# MAX6675.net
KiCad netlist of a schematic drawn in Altium Designer
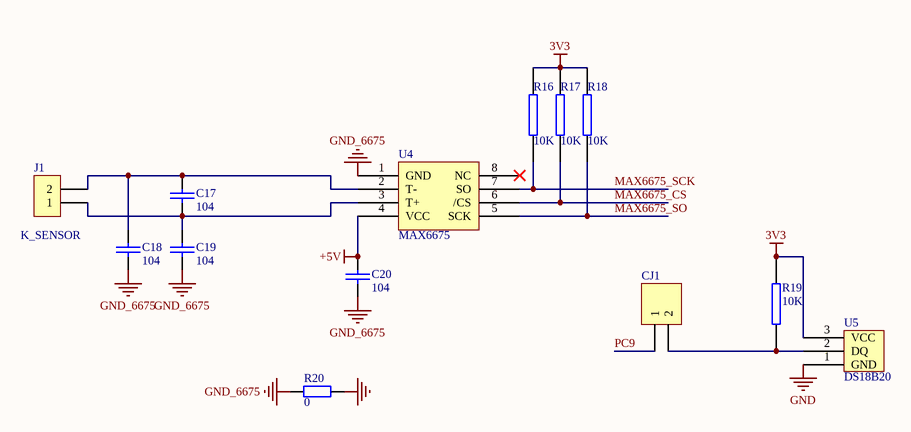
[diagram p0: MAX6675.SchDoc]

(export (version "E")
  (design (tool "Eeschema 10.0.6"))
  (components
    (comp (ref "C17")
      (value "104")
      (footprint "1206")
      (description "Capacitor")
      (libsource (lib "电容") (part "普通电容"))
    )
    (comp (ref "C18")
      (value "104")
      (footprint "1206")
      (description "Capacitor")
      (libsource (lib "电容") (part "普通电容"))
    )
    (comp (ref "C19")
      (value "104")
      (footprint "1206")
      (description "Capacitor")
      (libsource (lib "电容") (part "普通电容"))
    )
    (comp (ref "C20")
      (value "104")
      (footprint "1206")
      (description "Capacitor")
      (libsource (lib "电容") (part "普通电容"))
    )
    (comp (ref "CJ1")
      (value "DS18B20")
      (footprint "HDR1X2")
      (description "Header, 2-Pin")
      (fields (field (name "PUBLISHER") "Altium Limited"))
      (libsource (lib "底板封装库") (part "Header 2"))
    )
    (comp (ref "J1")
      (value "K_SENSOR")
      (footprint "OUT_CJ")
      (description "Connector")
      (libsource (lib "Miscellaneous Devices") (part "CON2"))
    )
    (comp (ref "R16") (value "10K") (footprint "1206") (libsource (lib "*") (part "RES2")))
    (comp (ref "R17") (value "10K") (footprint "1206") (libsource (lib "*") (part "RES2")))
    (comp (ref "R18") (value "10K") (footprint "1206") (libsource (lib "*") (part "RES2")))
    (comp (ref "R19") (value "10K") (footprint "1206") (libsource (lib "*") (part "RES2")))
    (comp (ref "R20")
      (value "0")
      (footprint "1206")
      (description "Resistor")
      (fields (field (name "PUBLISHER") "Altium Limited"))
      (libsource (lib "Miscellaneous Devices") (part "Res2"))
    )
    (comp (ref "U4") (value "MAX6675") (footprint "SO-8") (libsource (lib "温控库") (part "MAX6675")))
    (comp (ref "U5") (value "DS18B20") (footprint "DS18B20") (libsource (lib "底板封装库") (part "DS18B20")))
  )
  (nets
    (net (code "1") (name "+5V") (class "Default")
      (node (ref "C20") (pin "1") (pinfunction "1_1") (pintype "passive"))
      (node (ref "U4") (pin "4") (pinfunction "VCC_4") (pintype "passive"))
    )
    (net (code "2") (name "/MAX6675_CS") (class "Default")
      (node (ref "R17") (pin "1") (pinfunction "1_1") (pintype "passive"))
      (node (ref "U4") (pin "6") (pinfunction "/CS_6") (pintype "passive"))
    )
    (net (code "3") (name "/MAX6675_SCK") (class "Default")
      (node (ref "R16") (pin "1") (pinfunction "1_1") (pintype "passive"))
      (node (ref "U4") (pin "7") (pinfunction "SO_7") (pintype "passive"))
    )
    (net (code "4") (name "/MAX6675_SO") (class "Default")
      (node (ref "R18") (pin "1") (pinfunction "1_1") (pintype "passive"))
      (node (ref "U4") (pin "5") (pinfunction "SCK_5") (pintype "passive"))
    )
    (net (code "5") (name "/PC9") (class "Default")
      (node (ref "CJ1") (pin "1") (pinfunction "1_1") (pintype "passive"))
    )
    (net (code "6") (name "3V3") (class "Default")
      (node (ref "R16") (pin "2") (pinfunction "2_2") (pintype "passive"))
      (node (ref "R17") (pin "2") (pinfunction "2_2") (pintype "passive"))
      (node (ref "R18") (pin "2") (pinfunction "2_2") (pintype "passive"))
      (node (ref "R19") (pin "2") (pinfunction "2_2") (pintype "passive"))
      (node (ref "U5") (pin "3") (pinfunction "VCC_3") (pintype "passive"))
    )
    (net (code "7") (name "GND") (class "Default")
      (node (ref "R20") (pin "2") (pinfunction "2_2") (pintype "passive"))
      (node (ref "U5") (pin "1") (pinfunction "GND_1") (pintype "passive"))
    )
    (net (code "8") (name "GND_6675") (class "Default")
      (node (ref "C18") (pin "2") (pinfunction "2_2") (pintype "passive"))
      (node (ref "C19") (pin "2") (pinfunction "2_2") (pintype "passive"))
      (node (ref "C20") (pin "2") (pinfunction "2_2") (pintype "passive"))
      (node (ref "R20") (pin "1") (pinfunction "1_1") (pintype "passive"))
      (node (ref "U4") (pin "1") (pinfunction "GND_1") (pintype "passive"))
    )
    (net (code "9") (name "Net-(U4-T+)") (class "Default")
      (node (ref "C17") (pin "2") (pinfunction "2_2") (pintype "passive"))
      (node (ref "C19") (pin "1") (pinfunction "1_1") (pintype "passive"))
      (node (ref "J1") (pin "1") (pinfunction "1_1") (pintype "passive"))
      (node (ref "U4") (pin "3") (pinfunction "T+_3") (pintype "passive"))
    )
    (net (code "10") (name "Net-(U4-T-)") (class "Default")
      (node (ref "C17") (pin "1") (pinfunction "1_1") (pintype "passive"))
      (node (ref "C18") (pin "1") (pinfunction "1_1") (pintype "passive"))
      (node (ref "J1") (pin "2") (pinfunction "2_2") (pintype "passive"))
      (node (ref "U4") (pin "2") (pinfunction "T-_2") (pintype "passive"))
    )
    (net (code "11") (name "Net-(U5-DQ)") (class "Default")
      (node (ref "CJ1") (pin "2") (pinfunction "2_2") (pintype "passive"))
      (node (ref "R19") (pin "1") (pinfunction "1_1") (pintype "passive"))
      (node (ref "U5") (pin "2") (pinfunction "DQ_2") (pintype "passive"))
    )
    (net (code "12") (name "unconnected-(U4-NC-Pad8)") (class "Default")
      (node (ref "U4") (pin "8") (pinfunction "NC_8") (pintype "passive+no_connect"))
    )
  )
)
